# Main.net
KiCad netlist of a schematic drawn in Altium Designer
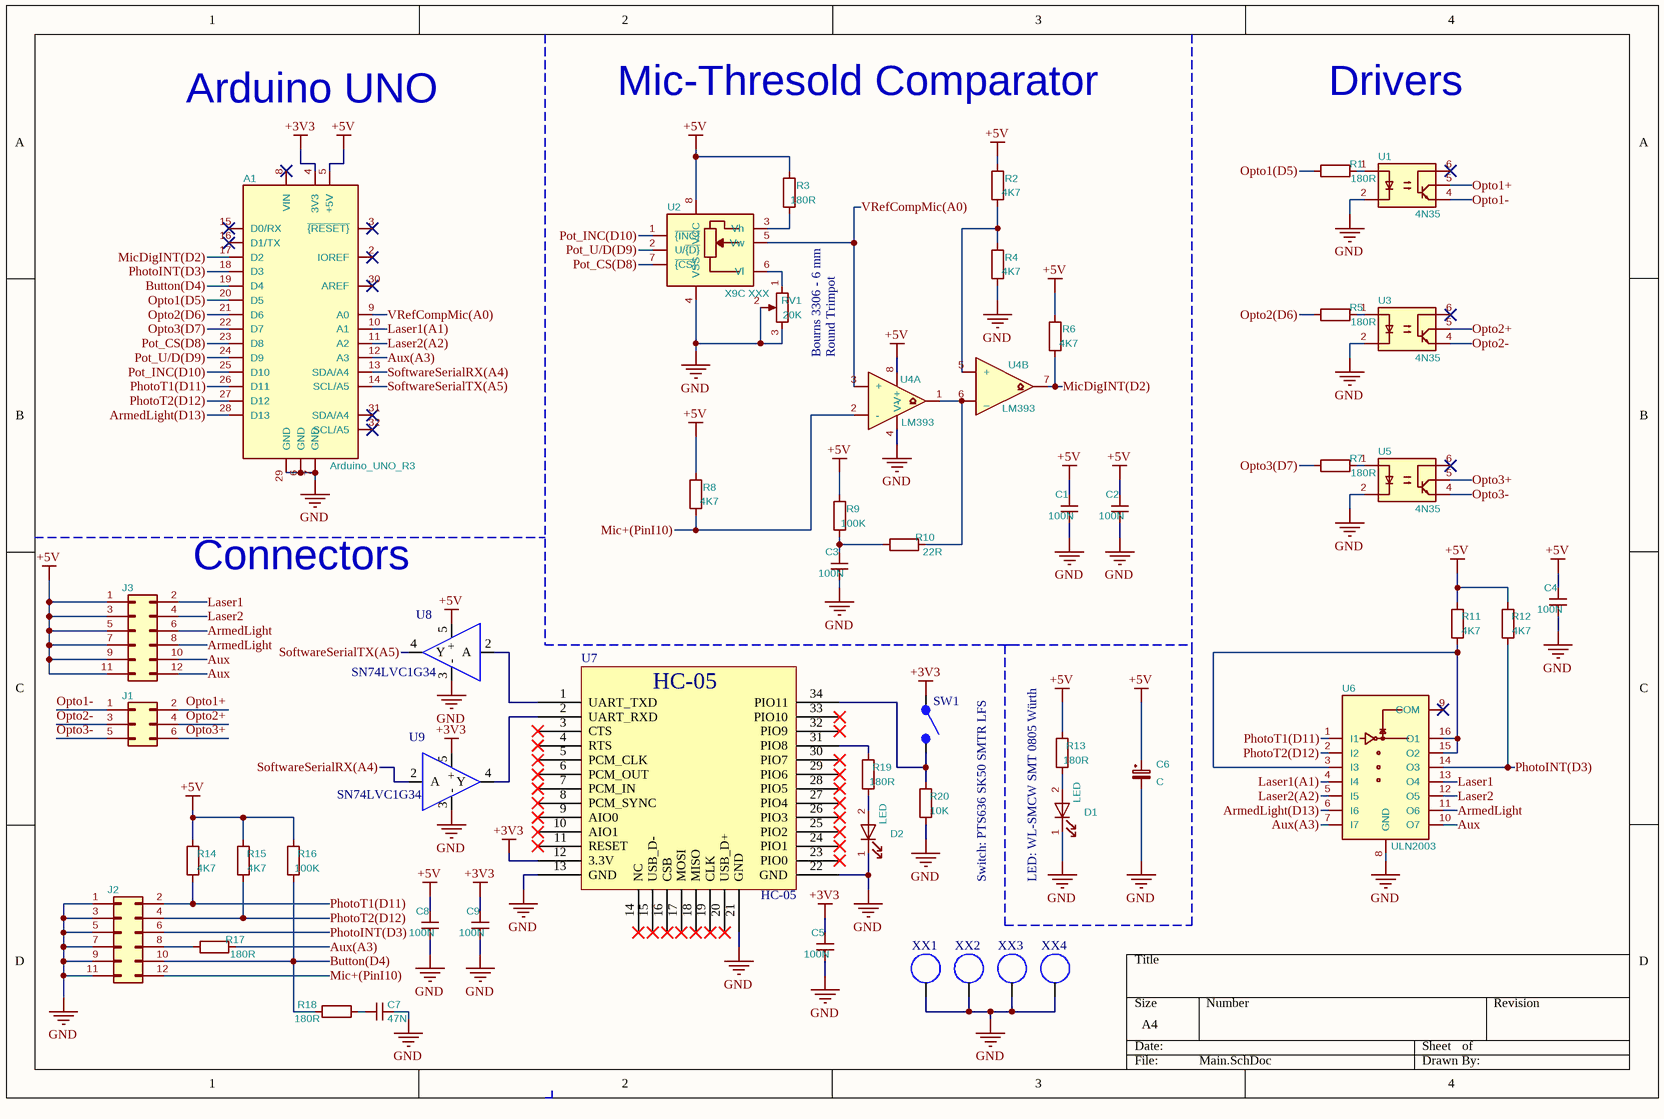
[diagram p0: Main.SchDoc]

(export (version "E")
  (design (tool "Eeschema 10.0.6"))
  (components
    (comp (ref "A1")
      (value "Arduino_UNO_R3")
      (footprint "ARDUINO_UNO_SHIELD")
      (libsource (lib "HSP-Arduino-Shield") (part "Arduino_UNO_R3"))
    )
    (comp (ref "C1")
      (value "100N")
      (footprint "C_0805_WAVESOLDER")
      (libsource (lib "HSP-Arduino-Shield") (part "C_NP"))
    )
    (comp (ref "C2")
      (value "100N")
      (footprint "C_0805_WAVESOLDER")
      (libsource (lib "HSP-Arduino-Shield") (part "C_NP"))
    )
    (comp (ref "C3")
      (value "100N")
      (footprint "C_0805_WAVESOLDER")
      (libsource (lib "HSP-Arduino-Shield") (part "C_NP"))
    )
    (comp (ref "C4")
      (value "100N")
      (footprint "C_0805_WAVESOLDER")
      (libsource (lib "HSP-Arduino-Shield") (part "C_NP"))
    )
    (comp (ref "C5")
      (value "100N")
      (footprint "C_0805_WAVESOLDER")
      (libsource (lib "HSP-Arduino-Shield") (part "C_NP"))
    )
    (comp (ref "C6")
      (value "C")
      (footprint "CAPAE7466X55M")
      (libsource (lib "HSP-Arduino-Shield") (part "C_POL"))
    )
    (comp (ref "C7")
      (value "47N")
      (footprint "C_0805_WAVESOLDER")
      (libsource (lib "HSP-Arduino-Shield") (part "C_NP"))
    )
    (comp (ref "C8")
      (value "100N")
      (footprint "C_0805_WAVESOLDER")
      (libsource (lib "HSP-Arduino-Shield") (part "C_NP"))
    )
    (comp (ref "C9")
      (value "100N")
      (footprint "C_0805_WAVESOLDER")
      (libsource (lib "HSP-Arduino-Shield") (part "C_NP"))
    )
    (comp (ref "D1")
      (value "LED")
      (footprint "Wurth_WL-SMCW_0805_LED")
      (libsource (lib "HSP-Arduino-Shield") (part "LED"))
    )
    (comp (ref "D2")
      (value "LED")
      (footprint "Wurth_WL-SMCW_0805_LED")
      (libsource (lib "HSP-Arduino-Shield") (part "LED"))
    )
    (comp (ref "J1")
      (value "OptocoupledOutputs")
      (footprint "PIN_HEADER_3X2")
      (libsource (lib "HSP-Arduino-Shield") (part "Conn_02x03_Odd_Even"))
    )
    (comp (ref "J2")
      (value "Open Collector Outputs")
      (footprint "PIN_HEADER_6X2")
      (libsource (lib "HSP-Arduino-Shield") (part "Conn_02x06_Odd_Even"))
    )
    (comp (ref "J3")
      (value "Open Collector Outputs")
      (footprint "PIN_HEADER_6X2")
      (libsource (lib "HSP-Arduino-Shield") (part "Conn_02x06_Odd_Even"))
    )
    (comp (ref "R1")
      (value "180R")
      (footprint "R_0805_WAVESOLDER")
      (libsource (lib "HSP-Arduino-Shield") (part "R"))
    )
    (comp (ref "R2") (value "4K7") (footprint "R_0805_WAVESOLDER") (libsource (lib "") (part "R_1")))
    (comp (ref "R3") (value "180R") (footprint "R_0805_WAVESOLDER") (libsource (lib "") (part "R_1")))
    (comp (ref "R4") (value "4K7") (footprint "R_0805_WAVESOLDER") (libsource (lib "") (part "R_1")))
    (comp (ref "R5")
      (value "180R")
      (footprint "R_0805_WAVESOLDER")
      (libsource (lib "HSP-Arduino-Shield") (part "R"))
    )
    (comp (ref "R6") (value "4K7") (footprint "R_0805_WAVESOLDER") (libsource (lib "") (part "R_1")))
    (comp (ref "R7")
      (value "180R")
      (footprint "R_0805_WAVESOLDER")
      (libsource (lib "HSP-Arduino-Shield") (part "R"))
    )
    (comp (ref "R8") (value "4K7") (footprint "R_0805_WAVESOLDER") (libsource (lib "") (part "R_1")))
    (comp (ref "R9") (value "100K") (footprint "R_0805_WAVESOLDER") (libsource (lib "") (part "R_1")))
    (comp (ref "R10")
      (value "22R")
      (footprint "R_0805_WAVESOLDER")
      (libsource (lib "HSP-Arduino-Shield") (part "R"))
    )
    (comp (ref "R11") (value "4K7") (footprint "R_0805_WAVESOLDER") (libsource (lib "") (part "R_1")))
    (comp (ref "R12") (value "4K7") (footprint "R_0805_WAVESOLDER") (libsource (lib "") (part "R_1")))
    (comp (ref "R13") (value "180R") (footprint "R_0805_WAVESOLDER") (libsource (lib "") (part "R_1")))
    (comp (ref "R14") (value "4K7") (footprint "R_0805_WAVESOLDER") (libsource (lib "") (part "R_1")))
    (comp (ref "R15") (value "4K7") (footprint "R_0805_WAVESOLDER") (libsource (lib "") (part "R_1")))
    (comp (ref "R16") (value "100K") (footprint "R_0805_WAVESOLDER") (libsource (lib "") (part "R_1")))
    (comp (ref "R17")
      (value "180R")
      (footprint "R_0805_WAVESOLDER")
      (libsource (lib "HSP-Arduino-Shield") (part "R"))
    )
    (comp (ref "R18")
      (value "180R")
      (footprint "R_0805_WAVESOLDER")
      (libsource (lib "HSP-Arduino-Shield") (part "R"))
    )
    (comp (ref "R19") (value "180R") (footprint "R_0805_WAVESOLDER") (libsource (lib "") (part "R_1")))
    (comp (ref "R20") (value "10K") (footprint "R_0805_WAVESOLDER") (libsource (lib "") (part "R_1")))
    (comp (ref "RV1")
      (value "20K")
      (footprint "Bourns_3306-6mm_Trimpot")
      (libsource (lib "HSP-Arduino-Shield") (part "R_Potentiometer"))
    )
    (comp (ref "SW1")
      (value "PTS636SK50SMTRLFS")
      (footprint "PTS636SK50SMTRLFS")
      (libsource (lib "HSP-Arduino-Shield") (part "PTS636SK50SMTRLFS"))
    )
    (comp (ref "U1")
      (value "4N35")
      (footprint "4N35_SMD-6")
      (libsource (lib "HSP-Arduino-Shield") (part "4N35"))
    )
    (comp (ref "U2")
      (value "X9C XXX")
      (footprint "X9C_XXX_SOIC8")
      (libsource (lib "HSP-Arduino-Shield") (part "X9C XXX"))
    )
    (comp (ref "U3")
      (value "4N35")
      (footprint "4N35_SMD-6")
      (libsource (lib "HSP-Arduino-Shield") (part "4N35"))
    )
    (comp (ref "U4")
      (value "LM393")
      (footprint "LM393M")
      (libsource (lib "HSP-Arduino-Shield") (part "LM393"))
    )
    (comp (ref "U5")
      (value "4N35")
      (footprint "4N35_SMD-6")
      (libsource (lib "HSP-Arduino-Shield") (part "4N35"))
    )
    (comp (ref "U6")
      (value "ULN2003")
      (footprint "ULN2003")
      (libsource (lib "HSP-Arduino-Shield") (part "ULN2003"))
    )
    (comp (ref "U7")
      (value "HC-05")
      (footprint "HC-05")
      (libsource (lib "HSP-Arduino-Shield") (part "HC-05"))
    )
    (comp (ref "U8")
      (value "SN74LVC1G34")
      (footprint "SN74LVC1G34")
      (libsource (lib "HSP-Arduino-Shield") (part "SN74LVC1G34"))
    )
    (comp (ref "U9")
      (value "SN74LVC1G34")
      (footprint "SN74LVC1G34")
      (libsource (lib "HSP-Arduino-Shield") (part "SN74LVC1G34"))
    )
    (comp (ref "XX1")
      (value "3.2MM_HOLE")
      (footprint "3.2MM_HOLE")
      (libsource (lib "HSP-Arduino-Shield") (part "3.2MM_HOLE"))
    )
    (comp (ref "XX2")
      (value "3.2MM_HOLE")
      (footprint "3.2MM_HOLE")
      (libsource (lib "HSP-Arduino-Shield") (part "3.2MM_HOLE"))
    )
    (comp (ref "XX3")
      (value "3.2MM_HOLE")
      (footprint "3.2MM_HOLE")
      (libsource (lib "HSP-Arduino-Shield") (part "3.2MM_HOLE"))
    )
    (comp (ref "XX4")
      (value "3.2MM_HOLE")
      (footprint "3.2MM_HOLE")
      (libsource (lib "HSP-Arduino-Shield") (part "3.2MM_HOLE"))
    )
  )
  (nets
    (net (code "1") (name "+3V3") (class "Default")
      (node (ref "A1") (pin "4") (pinfunction "3V3_4") (pintype "passive"))
      (node (ref "C5") (pin "2") (pinfunction "2_2") (pintype "passive"))
      (node (ref "C9") (pin "2") (pinfunction "2_2") (pintype "passive"))
      (node (ref "SW1") (pin "1") (pinfunction "1_1") (pintype "passive"))
      (node (ref "U7") (pin "12") (pinfunction "3.3V_12") (pintype "passive"))
      (node (ref "U9") (pin "5") (pinfunction "+_5") (pintype "passive"))
    )
    (net (code "2") (name "+5V") (class "Default")
      (node (ref "A1") (pin "5") (pinfunction "+5V_5") (pintype "passive"))
      (node (ref "C1") (pin "2") (pinfunction "2_2") (pintype "passive"))
      (node (ref "C2") (pin "2") (pinfunction "2_2") (pintype "passive"))
      (node (ref "C4") (pin "2") (pinfunction "2_2") (pintype "passive"))
      (node (ref "C6") (pin "1") (pinfunction "1_1") (pintype "passive"))
      (node (ref "C8") (pin "2") (pinfunction "2_2") (pintype "passive"))
      (node (ref "J3") (pin "1") (pinfunction "Pin_1_1") (pintype "passive"))
      (node (ref "J3") (pin "11") (pinfunction "Pin_11_11") (pintype "passive"))
      (node (ref "J3") (pin "3") (pinfunction "Pin_3_3") (pintype "passive"))
      (node (ref "J3") (pin "5") (pinfunction "Pin_5_5") (pintype "passive"))
      (node (ref "J3") (pin "7") (pinfunction "Pin_7_7") (pintype "passive"))
      (node (ref "J3") (pin "9") (pinfunction "Pin_9_9") (pintype "passive"))
      (node (ref "R11") (pin "1") (pinfunction "1_1") (pintype "passive"))
      (node (ref "R12") (pin "1") (pinfunction "1_1") (pintype "passive"))
      (node (ref "R13") (pin "1") (pinfunction "1_1") (pintype "passive"))
      (node (ref "R14") (pin "1") (pinfunction "1_1") (pintype "passive"))
      (node (ref "R15") (pin "1") (pinfunction "1_1") (pintype "passive"))
      (node (ref "R16") (pin "1") (pinfunction "1_1") (pintype "passive"))
      (node (ref "R2") (pin "1") (pinfunction "1_1") (pintype "passive"))
      (node (ref "R3") (pin "1") (pinfunction "1_1") (pintype "passive"))
      (node (ref "R6") (pin "1") (pinfunction "1_1") (pintype "passive"))
      (node (ref "R8") (pin "1") (pinfunction "1_1") (pintype "passive"))
      (node (ref "R9") (pin "1") (pinfunction "1_1") (pintype "passive"))
      (node (ref "U2") (pin "8") (pinfunction "VCC_8") (pintype "passive"))
      (node (ref "U4") (pin "8") (pinfunction "V+_8") (pintype "passive"))
      (node (ref "U8") (pin "5") (pinfunction "+_5") (pintype "passive"))
    )
    (net (code "3") (name "/ArmedLight") (class "Default")
      (node (ref "J3") (pin "6") (pinfunction "Pin_6_6") (pintype "passive"))
      (node (ref "J3") (pin "8") (pinfunction "Pin_8_8") (pintype "passive"))
      (node (ref "U6") (pin "11") (pinfunction "O6_11") (pintype "passive"))
    )
    (net (code "4") (name "/ArmedLight(D13)") (class "Default")
      (node (ref "A1") (pin "28") (pinfunction "D13_28") (pintype "passive"))
      (node (ref "U6") (pin "6") (pinfunction "I6_6") (pintype "passive"))
    )
    (net (code "5") (name "/Aux") (class "Default")
      (node (ref "J3") (pin "10") (pinfunction "Pin_10_10") (pintype "passive"))
      (node (ref "J3") (pin "12") (pinfunction "Pin_12_12") (pintype "passive"))
      (node (ref "U6") (pin "10") (pinfunction "O7_10") (pintype "passive"))
    )
    (net (code "6") (name "/Aux(A3)") (class "Default")
      (node (ref "A1") (pin "12") (pinfunction "A3_12") (pintype "passive"))
      (node (ref "R17") (pin "2") (pinfunction "2_2") (pintype "passive"))
      (node (ref "U6") (pin "7") (pinfunction "I7_7") (pintype "passive"))
    )
    (net (code "7") (name "/Button(D4)") (class "Default")
      (node (ref "A1") (pin "19") (pinfunction "D4_19") (pintype "passive"))
      (node (ref "J2") (pin "10") (pinfunction "Pin_10_10") (pintype "passive"))
      (node (ref "R16") (pin "2") (pinfunction "2_2") (pintype "passive"))
      (node (ref "R18") (pin "1") (pinfunction "1_1") (pintype "passive"))
    )
    (net (code "8") (name "/Laser1") (class "Default")
      (node (ref "J3") (pin "2") (pinfunction "Pin_2_2") (pintype "passive"))
      (node (ref "U6") (pin "13") (pinfunction "O4_13") (pintype "passive"))
    )
    (net (code "9") (name "/Laser1(A1)") (class "Default")
      (node (ref "A1") (pin "10") (pinfunction "A1_10") (pintype "passive"))
      (node (ref "U6") (pin "4") (pinfunction "I4_4") (pintype "passive"))
    )
    (net (code "10") (name "/Laser2") (class "Default")
      (node (ref "J3") (pin "4") (pinfunction "Pin_4_4") (pintype "passive"))
      (node (ref "U6") (pin "12") (pinfunction "O5_12") (pintype "passive"))
    )
    (net (code "11") (name "/Laser2(A2)") (class "Default")
      (node (ref "A1") (pin "11") (pinfunction "A2_11") (pintype "passive"))
      (node (ref "U6") (pin "5") (pinfunction "I5_5") (pintype "passive"))
    )
    (net (code "12") (name "/Mic+(PinI10)") (class "Default")
      (node (ref "J2") (pin "12") (pinfunction "Pin_12_12") (pintype "passive"))
      (node (ref "R8") (pin "2") (pinfunction "2_2") (pintype "passive"))
      (node (ref "U4") (pin "2") (pinfunction "-_2") (pintype "passive"))
    )
    (net (code "13") (name "/MicDigINT(D2)") (class "Default")
      (node (ref "A1") (pin "17") (pinfunction "D2_17") (pintype "passive"))
      (node (ref "R6") (pin "2") (pinfunction "2_2") (pintype "passive"))
      (node (ref "U4") (pin "7") (pinfunction "7_7") (pintype "passive"))
    )
    (net (code "14") (name "/Opto1(D5)") (class "Default")
      (node (ref "A1") (pin "20") (pinfunction "D5_20") (pintype "passive"))
      (node (ref "R1") (pin "1") (pinfunction "1_1") (pintype "passive"))
    )
    (net (code "15") (name "/Opto1+") (class "Default")
      (node (ref "J1") (pin "2") (pinfunction "Pin_2_2") (pintype "passive"))
      (node (ref "U1") (pin "5") (pinfunction "5_5") (pintype "passive"))
    )
    (net (code "16") (name "/Opto1-") (class "Default")
      (node (ref "J1") (pin "1") (pinfunction "Pin_1_1") (pintype "passive"))
      (node (ref "U1") (pin "4") (pinfunction "4_4") (pintype "passive"))
    )
    (net (code "17") (name "/Opto2(D6)") (class "Default")
      (node (ref "A1") (pin "21") (pinfunction "D6_21") (pintype "passive"))
      (node (ref "R5") (pin "1") (pinfunction "1_1") (pintype "passive"))
    )
    (net (code "18") (name "/Opto2+") (class "Default")
      (node (ref "J1") (pin "4") (pinfunction "Pin_4_4") (pintype "passive"))
      (node (ref "U3") (pin "5") (pinfunction "5_5") (pintype "passive"))
    )
    (net (code "19") (name "/Opto2-") (class "Default")
      (node (ref "J1") (pin "3") (pinfunction "Pin_3_3") (pintype "passive"))
      (node (ref "U3") (pin "4") (pinfunction "4_4") (pintype "passive"))
    )
    (net (code "20") (name "/Opto3(D7)") (class "Default")
      (node (ref "A1") (pin "22") (pinfunction "D7_22") (pintype "passive"))
      (node (ref "R7") (pin "1") (pinfunction "1_1") (pintype "passive"))
    )
    (net (code "21") (name "/Opto3+") (class "Default")
      (node (ref "J1") (pin "6") (pinfunction "Pin_6_6") (pintype "passive"))
      (node (ref "U5") (pin "5") (pinfunction "5_5") (pintype "passive"))
    )
    (net (code "22") (name "/Opto3-") (class "Default")
      (node (ref "J1") (pin "5") (pinfunction "Pin_5_5") (pintype "passive"))
      (node (ref "U5") (pin "4") (pinfunction "4_4") (pintype "passive"))
    )
    (net (code "23") (name "/PhotoINT(D3)") (class "Default")
      (node (ref "A1") (pin "18") (pinfunction "D3_18") (pintype "passive"))
      (node (ref "J2") (pin "6") (pinfunction "Pin_6_6") (pintype "passive"))
      (node (ref "R12") (pin "2") (pinfunction "2_2") (pintype "passive"))
      (node (ref "U6") (pin "14") (pinfunction "O3_14") (pintype "passive"))
    )
    (net (code "24") (name "/PhotoT1(D11)") (class "Default")
      (node (ref "A1") (pin "26") (pinfunction "D11_26") (pintype "passive"))
      (node (ref "J2") (pin "2") (pinfunction "Pin_2_2") (pintype "passive"))
      (node (ref "R14") (pin "2") (pinfunction "2_2") (pintype "passive"))
      (node (ref "U6") (pin "1") (pinfunction "I1_1") (pintype "passive"))
    )
    (net (code "25") (name "/PhotoT2(D12)") (class "Default")
      (node (ref "A1") (pin "27") (pinfunction "D12_27") (pintype "passive"))
      (node (ref "J2") (pin "4") (pinfunction "Pin_4_4") (pintype "passive"))
      (node (ref "R15") (pin "2") (pinfunction "2_2") (pintype "passive"))
      (node (ref "U6") (pin "2") (pinfunction "I2_2") (pintype "passive"))
    )
    (net (code "26") (name "/Pot_CS(D8)") (class "Default")
      (node (ref "A1") (pin "23") (pinfunction "D8_23") (pintype "passive"))
      (node (ref "U2") (pin "7") (pinfunction "~{{CS}}_7") (pintype "passive"))
    )
    (net (code "27") (name "/Pot_INC(D10)") (class "Default")
      (node (ref "A1") (pin "25") (pinfunction "D10_25") (pintype "passive"))
      (node (ref "U2") (pin "1") (pinfunction "~{{INC}}_1") (pintype "passive"))
    )
    (net (code "28") (name "/Pot_U{slash}D(D9)") (class "Default")
      (node (ref "A1") (pin "24") (pinfunction "D9_24") (pintype "passive"))
      (node (ref "U2") (pin "2") (pinfunction "U/~{{D}}_2") (pintype "passive"))
    )
    (net (code "29") (name "/SoftwareSerialRX(A4)") (class "Default")
      (node (ref "A1") (pin "13") (pinfunction "SDA/A4_13") (pintype "passive"))
      (node (ref "U9") (pin "2") (pinfunction "A_2") (pintype "passive"))
    )
    (net (code "30") (name "/SoftwareSerialTX(A5)") (class "Default")
      (node (ref "A1") (pin "14") (pinfunction "SCL/A5_14") (pintype "passive"))
      (node (ref "U8") (pin "4") (pinfunction "Y_4") (pintype "passive"))
    )
    (net (code "31") (name "/VRefCompMic(A0)") (class "Default")
      (node (ref "A1") (pin "9") (pinfunction "A0_9") (pintype "passive"))
      (node (ref "U2") (pin "5") (pinfunction "Vw_5") (pintype "passive"))
      (node (ref "U4") (pin "3") (pinfunction "+_3") (pintype "passive"))
    )
    (net (code "32") (name "GND") (class "Default")
      (node (ref "A1") (pin "29") (pinfunction "GND_29") (pintype "passive"))
      (node (ref "A1") (pin "6") (pinfunction "GND_6") (pintype "passive"))
      (node (ref "A1") (pin "7") (pinfunction "GND_7") (pintype "passive"))
      (node (ref "C1") (pin "1") (pinfunction "1_1") (pintype "passive"))
      (node (ref "C2") (pin "1") (pinfunction "1_1") (pintype "passive"))
      (node (ref "C3") (pin "1") (pinfunction "1_1") (pintype "passive"))
      (node (ref "C4") (pin "1") (pinfunction "1_1") (pintype "passive"))
      (node (ref "C5") (pin "1") (pinfunction "1_1") (pintype "passive"))
      (node (ref "C6") (pin "2") (pinfunction "2_2") (pintype "passive"))
      (node (ref "C7") (pin "2") (pinfunction "2_2") (pintype "passive"))
      (node (ref "C8") (pin "1") (pinfunction "1_1") (pintype "passive"))
      (node (ref "C9") (pin "1") (pinfunction "1_1") (pintype "passive"))
      (node (ref "D1") (pin "1") (pinfunction "K_1") (pintype "passive"))
      (node (ref "D2") (pin "1") (pinfunction "K_1") (pintype "passive"))
      (node (ref "J2") (pin "1") (pinfunction "Pin_1_1") (pintype "passive"))
      (node (ref "J2") (pin "11") (pinfunction "Pin_11_11") (pintype "passive"))
      (node (ref "J2") (pin "3") (pinfunction "Pin_3_3") (pintype "passive"))
      (node (ref "J2") (pin "5") (pinfunction "Pin_5_5") (pintype "passive"))
      (node (ref "J2") (pin "7") (pinfunction "Pin_7_7") (pintype "passive"))
      (node (ref "J2") (pin "9") (pinfunction "Pin_9_9") (pintype "passive"))
      (node (ref "R20") (pin "2") (pinfunction "2_2") (pintype "passive"))
      (node (ref "R4") (pin "2") (pinfunction "2_2") (pintype "passive"))
      (node (ref "RV1") (pin "2") (pinfunction "2_2") (pintype "passive"))
      (node (ref "RV1") (pin "3") (pinfunction "3_3") (pintype "passive"))
      (node (ref "U1") (pin "2") (pinfunction "2_2") (pintype "passive"))
      (node (ref "U2") (pin "4") (pinfunction "VSS_4") (pintype "passive"))
      (node (ref "U3") (pin "2") (pinfunction "2_2") (pintype "passive"))
      (node (ref "U4") (pin "4") (pinfunction "V-_4") (pintype "passive"))
      (node (ref "U5") (pin "2") (pinfunction "2_2") (pintype "passive"))
      (node (ref "U6") (pin "8") (pinfunction "GND_8") (pintype "passive"))
      (node (ref "U7") (pin "13") (pinfunction "GND_13") (pintype "passive"))
      (node (ref "U7") (pin "21") (pinfunction "GND_21") (pintype "passive"))
      (node (ref "U7") (pin "22") (pinfunction "GND_22") (pintype "passive"))
      (node (ref "U8") (pin "3") (pinfunction "-_3") (pintype "passive"))
      (node (ref "U9") (pin "3") (pinfunction "-_3") (pintype "passive"))
      (node (ref "XX1") (pin "1") (pinfunction "1_1") (pintype "passive"))
      (node (ref "XX2") (pin "1") (pinfunction "1_1") (pintype "passive"))
      (node (ref "XX3") (pin "1") (pinfunction "1_1") (pintype "passive"))
      (node (ref "XX4") (pin "1") (pinfunction "1_1") (pintype "passive"))
    )
    (net (code "33") (name "Net-(C3-Pad2)") (class "Default")
      (node (ref "C3") (pin "2") (pinfunction "2_2") (pintype "passive"))
      (node (ref "R10") (pin "1") (pinfunction "1_1") (pintype "passive"))
      (node (ref "R9") (pin "2") (pinfunction "2_2") (pintype "passive"))
    )
    (net (code "34") (name "Net-(C7-Pad1)") (class "Default")
      (node (ref "C7") (pin "1") (pinfunction "1_1") (pintype "passive"))
      (node (ref "R18") (pin "2") (pinfunction "2_2") (pintype "passive"))
    )
    (net (code "35") (name "Net-(D1-A)") (class "Default")
      (node (ref "D1") (pin "2") (pinfunction "A_2") (pintype "passive"))
      (node (ref "R13") (pin "2") (pinfunction "2_2") (pintype "passive"))
    )
    (net (code "36") (name "Net-(D2-A)") (class "Default")
      (node (ref "D2") (pin "2") (pinfunction "A_2") (pintype "passive"))
      (node (ref "R19") (pin "2") (pinfunction "2_2") (pintype "passive"))
    )
    (net (code "37") (name "Net-(J2-Pin_8)") (class "Default")
      (node (ref "J2") (pin "8") (pinfunction "Pin_8_8") (pintype "passive"))
      (node (ref "R17") (pin "1") (pinfunction "1_1") (pintype "passive"))
    )
    (net (code "38") (name "Net-(R1-Pad2)") (class "Default")
      (node (ref "R1") (pin "2") (pinfunction "2_2") (pintype "passive"))
      (node (ref "U1") (pin "1") (pinfunction "1_1") (pintype "passive"))
    )
    (net (code "39") (name "Net-(R5-Pad2)") (class "Default")
      (node (ref "R5") (pin "2") (pinfunction "2_2") (pintype "passive"))
      (node (ref "U3") (pin "1") (pinfunction "1_1") (pintype "passive"))
    )
    (net (code "40") (name "Net-(R7-Pad2)") (class "Default")
      (node (ref "R7") (pin "2") (pinfunction "2_2") (pintype "passive"))
      (node (ref "U5") (pin "1") (pinfunction "1_1") (pintype "passive"))
    )
    (net (code "41") (name "Net-(U2-Vh)") (class "Default")
      (node (ref "R3") (pin "2") (pinfunction "2_2") (pintype "passive"))
      (node (ref "U2") (pin "3") (pinfunction "Vh_3") (pintype "passive"))
    )
    (net (code "42") (name "Net-(U2-Vl)") (class "Default")
      (node (ref "RV1") (pin "1") (pinfunction "1_1") (pintype "passive"))
      (node (ref "U2") (pin "6") (pinfunction "Vl_6") (pintype "passive"))
    )
    (net (code "43") (name "Net-(U4B-+)") (class "Default")
      (node (ref "R2") (pin "2") (pinfunction "2_2") (pintype "passive"))
      (node (ref "R4") (pin "1") (pinfunction "1_1") (pintype "passive"))
      (node (ref "U4") (pin "5") (pinfunction "+_5") (pintype "passive"))
    )
    (net (code "44") (name "Net-(U4B-_)") (class "Default")
      (node (ref "R10") (pin "2") (pinfunction "2_2") (pintype "passive"))
      (node (ref "U4") (pin "1") (pinfunction "1_1") (pintype "passive"))
      (node (ref "U4") (pin "6") (pinfunction "__6") (pintype "passive"))
    )
    (net (code "45") (name "Net-(U6-I3)") (class "Default")
      (node (ref "R11") (pin "2") (pinfunction "2_2") (pintype "passive"))
      (node (ref "U6") (pin "15") (pinfunction "O2_15") (pintype "passive"))
      (node (ref "U6") (pin "16") (pinfunction "O1_16") (pintype "passive"))
      (node (ref "U6") (pin "3") (pinfunction "I3_3") (pintype "passive"))
    )
    (net (code "46") (name "Net-(U7-PIO8)") (class "Default")
      (node (ref "R19") (pin "1") (pinfunction "1_1") (pintype "passive"))
      (node (ref "U7") (pin "31") (pinfunction "PIO8_31") (pintype "passive"))
    )
    (net (code "47") (name "Net-(U7-PIO11)") (class "Default")
      (node (ref "R20") (pin "1") (pinfunction "1_1") (pintype "passive"))
      (node (ref "SW1") (pin "2") (pinfunction "2_2") (pintype "passive"))
      (node (ref "U7") (pin "34") (pinfunction "PIO11_34") (pintype "passive"))
    )
    (net (code "48") (name "Net-(U7-UART_RXD)") (class "Default")
      (node (ref "U7") (pin "2") (pinfunction "UART_RXD_2") (pintype "passive"))
      (node (ref "U9") (pin "4") (pinfunction "Y_4") (pintype "passive"))
    )
    (net (code "49") (name "Net-(U7-UART_TXD)") (class "Default")
      (node (ref "U7") (pin "1") (pinfunction "UART_TXD_1") (pintype "passive"))
      (node (ref "U8") (pin "2") (pinfunction "A_2") (pintype "passive"))
    )
    (net (code "50") (name "unconnected-(A1-AREF-Pad30)") (class "Default")
      (node (ref "A1") (pin "30") (pinfunction "AREF_30") (pintype "passive+no_connect"))
    )
    (net (code "51") (name "unconnected-(A1-D0{slash}RX-Pad15)") (class "Default")
      (node (ref "A1") (pin "15") (pinfunction "D0/RX_15") (pintype "passive+no_connect"))
    )
    (net (code "52") (name "unconnected-(A1-D1{slash}TX-Pad16)") (class "Default")
      (node (ref "A1") (pin "16") (pinfunction "D1/TX_16") (pintype "passive+no_connect"))
    )
    (net (code "53") (name "unconnected-(A1-IOREF-Pad2)") (class "Default")
      (node (ref "A1") (pin "2") (pinfunction "IOREF_2") (pintype "passive+no_connect"))
    )
    (net (code "54") (name "unconnected-(A1-NC-Pad1)") (class "Default")
      (node (ref "A1") (pin "1") (pinfunction "NC_1") (pintype "passive"))
    )
    (net (code "55") (name "unconnected-(A1-SCL{slash}A5-Pad32)") (class "Default")
      (node (ref "A1") (pin "32") (pinfunction "SCL/A5_32") (pintype "passive+no_connect"))
    )
    (net (code "56") (name "unconnected-(A1-SDA{slash}A4-Pad31)") (class "Default")
      (node (ref "A1") (pin "31") (pinfunction "SDA/A4_31") (pintype "passive+no_connect"))
    )
    (net (code "57") (name "unconnected-(A1-VIN-Pad8)") (class "Default")
      (node (ref "A1") (pin "8") (pinfunction "VIN_8") (pintype "passive+no_connect"))
    )
    (net (code "58") (name "unconnected-(A1-~{{RESET}}-Pad3)") (class "Default")
      (node (ref "A1") (pin "3") (pinfunction "~{{RESET}}_3") (pintype "passive+no_connect"))
    )
    (net (code "59") (name "unconnected-(U1-NC-Pad3)") (class "Default")
      (node (ref "U1") (pin "3") (pinfunction "NC_3") (pintype "passive"))
    )
    (net (code "60") (name "unconnected-(U1-Pad6)") (class "Default")
      (node (ref "U1") (pin "6") (pinfunction "6_6") (pintype "passive+no_connect"))
    )
    (net (code "61") (name "unconnected-(U3-NC-Pad3)") (class "Default")
      (node (ref "U3") (pin "3") (pinfunction "NC_3") (pintype "passive"))
    )
    (net (code "62") (name "unconnected-(U3-Pad6)") (class "Default")
      (node (ref "U3") (pin "6") (pinfunction "6_6") (pintype "passive+no_connect"))
    )
    (net (code "63") (name "unconnected-(U5-NC-Pad3)") (class "Default")
      (node (ref "U5") (pin "3") (pinfunction "NC_3") (pintype "passive"))
    )
    (net (code "64") (name "unconnected-(U5-Pad6)") (class "Default")
      (node (ref "U5") (pin "6") (pinfunction "6_6") (pintype "passive+no_connect"))
    )
    (net (code "65") (name "unconnected-(U6-COM-Pad9)") (class "Default")
      (node (ref "U6") (pin "9") (pinfunction "COM_9") (pintype "passive+no_connect"))
    )
    (net (code "66") (name "unconnected-(U7-AIO0-Pad9)") (class "Default")
      (node (ref "U7") (pin "9") (pinfunction "AIO0_9") (pintype "passive+no_connect"))
    )
    (net (code "67") (name "unconnected-(U7-AIO1-Pad10)") (class "Default")
      (node (ref "U7") (pin "10") (pinfunction "AIO1_10") (pintype "passive+no_connect"))
    )
    (net (code "68") (name "unconnected-(U7-CLK-Pad19)") (class "Default")
      (node (ref "U7") (pin "19") (pinfunction "CLK_19") (pintype "passive+no_connect"))
    )
    (net (code "69") (name "unconnected-(U7-CSB-Pad16)") (class "Default")
      (node (ref "U7") (pin "16") (pinfunction "CSB_16") (pintype "passive+no_connect"))
    )
    (net (code "70") (name "unconnected-(U7-CTS-Pad3)") (class "Default")
      (node (ref "U7") (pin "3") (pinfunction "CTS_3") (pintype "passive+no_connect"))
    )
    (net (code "71") (name "unconnected-(U7-MISO-Pad18)") (class "Default")
      (node (ref "U7") (pin "18") (pinfunction "MISO_18") (pintype "passive+no_connect"))
    )
    (net (code "72") (name "unconnected-(U7-MOSI-Pad17)") (class "Default")
      (node (ref "U7") (pin "17") (pinfunction "MOSI_17") (pintype "passive+no_connect"))
    )
    (net (code "73") (name "unconnected-(U7-NC-Pad14)") (class "Default")
      (node (ref "U7") (pin "14") (pinfunction "NC_14") (pintype "passive+no_connect"))
    )
    (net (code "74") (name "unconnected-(U7-PCM_CLK-Pad5)") (class "Default")
      (node (ref "U7") (pin "5") (pinfunction "PCM_CLK_5") (pintype "passive+no_connect"))
    )
    (net (code "75") (name "unconnected-(U7-PCM_IN-Pad7)") (class "Default")
      (node (ref "U7") (pin "7") (pinfunction "PCM_IN_7") (pintype "passive+no_connect"))
    )
    (net (code "76") (name "unconnected-(U7-PCM_OUT-Pad6)") (class "Default")
      (node (ref "U7") (pin "6") (pinfunction "PCM_OUT_6") (pintype "passive+no_connect"))
    )
    (net (code "77") (name "unconnected-(U7-PCM_SYNC-Pad8)") (class "Default")
      (node (ref "U7") (pin "8") (pinfunction "PCM_SYNC_8") (pintype "passive+no_connect"))
    )
    (net (code "78") (name "unconnected-(U7-PIO0-Pad23)") (class "Default")
      (node (ref "U7") (pin "23") (pinfunction "PIO0_23") (pintype "passive+no_connect"))
    )
    (net (code "79") (name "unconnected-(U7-PIO1-Pad24)") (class "Default")
      (node (ref "U7") (pin "24") (pinfunction "PIO1_24") (pintype "passive+no_connect"))
    )
    (net (code "80") (name "unconnected-(U7-PIO2-Pad25)") (class "Default")
      (node (ref "U7") (pin "25") (pinfunction "PIO2_25") (pintype "passive+no_connect"))
    )
    (net (code "81") (name "unconnected-(U7-PIO3-Pad26)") (class "Default")
      (node (ref "U7") (pin "26") (pinfunction "PIO3_26") (pintype "passive+no_connect"))
    )
    (net (code "82") (name "unconnected-(U7-PIO4-Pad27)") (class "Default")
      (node (ref "U7") (pin "27") (pinfunction "PIO4_27") (pintype "passive+no_connect"))
    )
    (net (code "83") (name "unconnected-(U7-PIO5-Pad28)") (class "Default")
      (node (ref "U7") (pin "28") (pinfunction "PIO5_28") (pintype "passive+no_connect"))
    )
    (net (code "84") (name "unconnected-(U7-PIO6-Pad29)") (class "Default")
      (node (ref "U7") (pin "29") (pinfunction "PIO6_29") (pintype "passive+no_connect"))
    )
    (net (code "85") (name "unconnected-(U7-PIO7-Pad30)") (class "Default")
      (node (ref "U7") (pin "30") (pinfunction "PIO7_30") (pintype "passive+no_connect"))
    )
    (net (code "86") (name "unconnected-(U7-PIO9-Pad32)") (class "Default")
      (node (ref "U7") (pin "32") (pinfunction "PIO9_32") (pintype "passive+no_connect"))
    )
    (net (code "87") (name "unconnected-(U7-PIO10-Pad33)") (class "Default")
      (node (ref "U7") (pin "33") (pinfunction "PIO10_33") (pintype "passive+no_connect"))
    )
    (net (code "88") (name "unconnected-(U7-RESET-Pad11)") (class "Default")
      (node (ref "U7") (pin "11") (pinfunction "RESET_11") (pintype "passive+no_connect"))
    )
    (net (code "89") (name "unconnected-(U7-RTS-Pad4)") (class "Default")
      (node (ref "U7") (pin "4") (pinfunction "RTS_4") (pintype "passive+no_connect"))
    )
    (net (code "90") (name "unconnected-(U7-USB_D+-Pad20)") (class "Default")
      (node (ref "U7") (pin "20") (pinfunction "USB_D+_20") (pintype "passive+no_connect"))
    )
    (net (code "91") (name "unconnected-(U7-USB_D--Pad15)") (class "Default")
      (node (ref "U7") (pin "15") (pinfunction "USB_D-_15") (pintype "passive+no_connect"))
    )
  )
)
